# Arduino_clock.net
KiCad netlist of a schematic drawn in Altium Designer
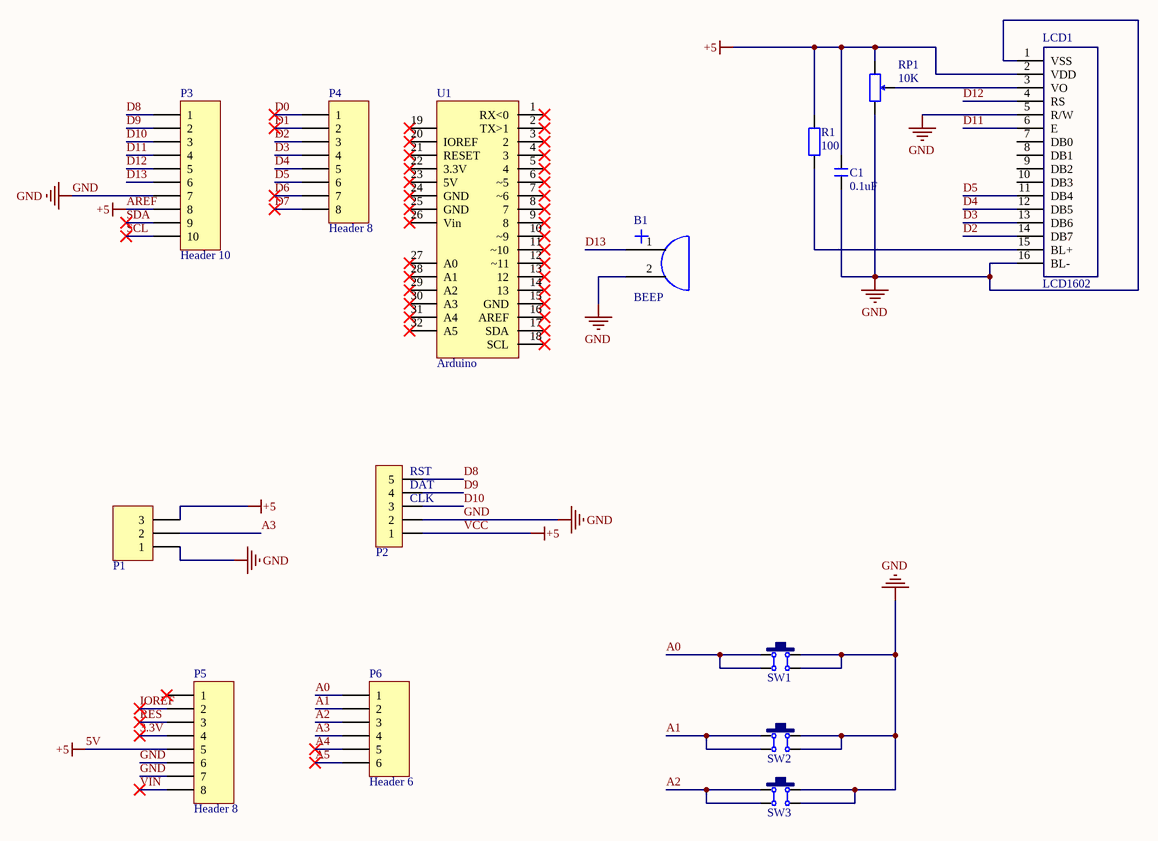
[diagram p0: Arduino_clock.SchDoc]

(export (version "E")
  (design (tool "Eeschema 10.0.6"))
  (components
    (comp (ref "B1")
      (value "BEEP")
      (footprint "Beep")
      (description "蜂鸣器")
      (libsource (lib "Fszhang") (part "BEEP"))
    )
    (comp (ref "C1")
      (value "0.1uF")
      (footprint "CY 5*7*2.5")
      (description "高压陶瓷电容，Y电容")
      (fields (field (name "版权归属") "源创客"))
      (libsource (lib "3.1   - 电阻-电容-电感") (part "C-CY"))
    )
    (comp (ref "LCD1") (value "LCD1602") (footprint "1602-1") (libsource (lib "LCD") (part "LCD1602")))
    (comp (ref "P1")
      (value "Header 3")
      (footprint "HDR2.54-LI-3P")
      (description "接插件")
      (fields (field (name "PUBLISHER") "Altium Limited"))
      (libsource (lib "Fszhang") (part "Header 3"))
    )
    (comp (ref "P2")
      (value "HDR-1X5")
      (footprint "HDR2.54-LI-5P")
      (description "5P接插件")
      (fields (field (name "版权归属") "源创客"))
      (libsource (lib "4.5   - 接插件-脚距2.54") (part "Header 5"))
    )
    (comp (ref "P3")
      (value "Header 10")
      (footprint "HDR2.54-LI-10P")
      (description "Header, 10-Pin")
      (fields (field (name "PUBLISHER") "Altium Limited"))
      (libsource (lib "Fszhang") (part "Header 10"))
    )
    (comp (ref "P4")
      (value "Header 8")
      (footprint "HDR2.54-LI-8P")
      (description "Header, 8-Pin")
      (fields (field (name "PUBLISHER") "Altium Limited"))
      (libsource (lib "Fszhang") (part "Header 8"))
    )
    (comp (ref "P5")
      (value "Header 8")
      (footprint "HDR2.54-LI-8P")
      (description "Header, 8-Pin")
      (fields (field (name "PUBLISHER") "Altium Limited"))
      (libsource (lib "Fszhang") (part "Header 8"))
    )
    (comp (ref "P6")
      (value "Header 6")
      (footprint "HDR2.54-LI-6P")
      (description "接插件")
      (fields (field (name "PUBLISHER") "Altium Limited"))
      (libsource (lib "Fszhang") (part "Header 6"))
    )
    (comp (ref "R1")
      (value "100")
      (footprint "AXIAL0.4-1/4W")
      (description "贴片电阻")
      (fields (field (name "版权归属") "源创客"))
      (libsource (lib "3.1   - 电阻-电容-电感") (part "R"))
    )
    (comp (ref "RP1")
      (value "10K")
      (footprint "RM065")
      (description "插件单联电位器")
      (fields (field (name "版权归属") "源创客"))
      (libsource (lib "3.1   - 电阻-电容-电感") (part "RP-ID"))
    )
    (comp (ref "SW1")
      (value "6x6x5")
      (footprint "TSW DIP-6*6*6")
      (description "直插6x6轻触开关")
      (fields (field (name "版权归属") "源创客"))
      (libsource (lib "5.1   - 按键-开关") (part "TSW DIP-6x6"))
    )
    (comp (ref "SW2")
      (value "6x6x5")
      (footprint "TSW DIP-6*6*6")
      (description "直插6x6轻触开关")
      (fields (field (name "版权归属") "源创客"))
      (libsource (lib "5.1   - 按键-开关") (part "TSW DIP-6x6"))
    )
    (comp (ref "SW3")
      (value "6x6x5")
      (footprint "TSW DIP-6*6*6")
      (description "直插6x6轻触开关")
      (fields (field (name "版权归属") "源创客"))
      (libsource (lib "5.1   - 按键-开关") (part "TSW DIP-6x6"))
    )
    (comp (ref "U1")
      (value "Arduino")
      (footprint "Arduino-UNO")
      (libsource (lib "LixhSch") (part "Arduino-UNO"))
    )
  )
  (nets
    (net (code "1") (name "+5") (class "Default")
      (node (ref "C1") (pin "2") (pinfunction "2_2") (pintype "passive"))
      (node (ref "LCD1") (pin "2") (pinfunction "VDD_2") (pintype "passive"))
      (node (ref "P1") (pin "3") (pinfunction "3_3") (pintype "passive"))
      (node (ref "P2") (pin "1") (pinfunction "1_1") (pintype "passive"))
      (node (ref "P3") (pin "8") (pinfunction "8_8") (pintype "passive"))
      (node (ref "P5") (pin "5") (pinfunction "5_5") (pintype "passive"))
      (node (ref "R1") (pin "2") (pinfunction "2_2") (pintype "passive"))
      (node (ref "RP1") (pin "1") (pinfunction "1_1") (pintype "passive"))
    )
    (net (code "2") (name "/3.3V") (class "Default")
      (node (ref "P5") (pin "4") (pinfunction "4_4") (pintype "passive+no_connect"))
    )
    (net (code "3") (name "/A0") (class "Default")
      (node (ref "P6") (pin "1") (pinfunction "1_1") (pintype "passive"))
      (node (ref "SW1") (pin "1") (pinfunction "1_1") (pintype "passive"))
      (node (ref "SW1") (pin "4") (pinfunction "4_4") (pintype "passive"))
    )
    (net (code "4") (name "/A1") (class "Default")
      (node (ref "P6") (pin "2") (pinfunction "2_2") (pintype "passive"))
      (node (ref "SW2") (pin "1") (pinfunction "1_1") (pintype "passive"))
      (node (ref "SW2") (pin "4") (pinfunction "4_4") (pintype "passive"))
    )
    (net (code "5") (name "/A2") (class "Default")
      (node (ref "P6") (pin "3") (pinfunction "3_3") (pintype "passive"))
      (node (ref "SW3") (pin "1") (pinfunction "1_1") (pintype "passive"))
      (node (ref "SW3") (pin "4") (pinfunction "4_4") (pintype "passive"))
    )
    (net (code "6") (name "/A3") (class "Default")
      (node (ref "P1") (pin "2") (pinfunction "2_2") (pintype "passive"))
      (node (ref "P6") (pin "4") (pinfunction "4_4") (pintype "passive"))
    )
    (net (code "7") (name "/A4") (class "Default")
      (node (ref "P6") (pin "5") (pinfunction "5_5") (pintype "passive+no_connect"))
    )
    (net (code "8") (name "/A5") (class "Default")
      (node (ref "P6") (pin "6") (pinfunction "6_6") (pintype "passive+no_connect"))
    )
    (net (code "9") (name "/D0") (class "Default")
      (node (ref "P4") (pin "1") (pinfunction "1_1") (pintype "passive+no_connect"))
    )
    (net (code "10") (name "/D1") (class "Default")
      (node (ref "P4") (pin "2") (pinfunction "2_2") (pintype "passive+no_connect"))
    )
    (net (code "11") (name "/D2") (class "Default")
      (node (ref "LCD1") (pin "14") (pinfunction "DB7_14") (pintype "passive"))
      (node (ref "P4") (pin "3") (pinfunction "3_3") (pintype "passive"))
    )
    (net (code "12") (name "/D3") (class "Default")
      (node (ref "LCD1") (pin "13") (pinfunction "DB6_13") (pintype "passive"))
      (node (ref "P4") (pin "4") (pinfunction "4_4") (pintype "passive"))
    )
    (net (code "13") (name "/D4") (class "Default")
      (node (ref "LCD1") (pin "12") (pinfunction "DB5_12") (pintype "passive"))
      (node (ref "P4") (pin "5") (pinfunction "5_5") (pintype "passive"))
    )
    (net (code "14") (name "/D5") (class "Default")
      (node (ref "LCD1") (pin "11") (pinfunction "DB4_11") (pintype "passive"))
      (node (ref "P4") (pin "6") (pinfunction "6_6") (pintype "passive"))
    )
    (net (code "15") (name "/D6") (class "Default")
      (node (ref "P4") (pin "7") (pinfunction "7_7") (pintype "passive+no_connect"))
    )
    (net (code "16") (name "/D7") (class "Default")
      (node (ref "P4") (pin "8") (pinfunction "8_8") (pintype "passive+no_connect"))
    )
    (net (code "17") (name "/D8") (class "Default")
      (node (ref "P2") (pin "5") (pinfunction "5_5") (pintype "passive"))
      (node (ref "P3") (pin "1") (pinfunction "1_1") (pintype "passive"))
    )
    (net (code "18") (name "/D9") (class "Default")
      (node (ref "P2") (pin "4") (pinfunction "4_4") (pintype "passive"))
      (node (ref "P3") (pin "2") (pinfunction "2_2") (pintype "passive"))
    )
    (net (code "19") (name "/D10") (class "Default")
      (node (ref "P2") (pin "3") (pinfunction "3_3") (pintype "passive"))
      (node (ref "P3") (pin "3") (pinfunction "3_3") (pintype "passive"))
    )
    (net (code "20") (name "/D11") (class "Default")
      (node (ref "LCD1") (pin "6") (pinfunction "E_6") (pintype "passive"))
      (node (ref "P3") (pin "4") (pinfunction "4_4") (pintype "passive"))
    )
    (net (code "21") (name "/D12") (class "Default")
      (node (ref "LCD1") (pin "4") (pinfunction "RS_4") (pintype "passive"))
      (node (ref "P3") (pin "5") (pinfunction "5_5") (pintype "passive"))
    )
    (net (code "22") (name "/D13") (class "Default")
      (node (ref "B1") (pin "1") (pinfunction "0_1") (pintype "passive"))
      (node (ref "P3") (pin "6") (pinfunction "6_6") (pintype "passive"))
    )
    (net (code "23") (name "/IOREF") (class "Default")
      (node (ref "P5") (pin "2") (pinfunction "2_2") (pintype "passive+no_connect"))
    )
    (net (code "24") (name "/RES") (class "Default")
      (node (ref "P5") (pin "3") (pinfunction "3_3") (pintype "passive+no_connect"))
    )
    (net (code "25") (name "/SCL") (class "Default")
      (node (ref "P3") (pin "10") (pinfunction "10_10") (pintype "passive+no_connect"))
    )
    (net (code "26") (name "/SDA") (class "Default")
      (node (ref "P3") (pin "9") (pinfunction "9_9") (pintype "passive+no_connect"))
    )
    (net (code "27") (name "/VIN") (class "Default")
      (node (ref "P5") (pin "8") (pinfunction "8_8") (pintype "passive+no_connect"))
    )
    (net (code "28") (name "GND") (class "Default")
      (node (ref "B1") (pin "2") (pinfunction "1_2") (pintype "passive"))
      (node (ref "C1") (pin "1") (pinfunction "1_1") (pintype "passive"))
      (node (ref "LCD1") (pin "1") (pinfunction "VSS_1") (pintype "passive"))
      (node (ref "LCD1") (pin "16") (pinfunction "BL-_16") (pintype "passive"))
      (node (ref "LCD1") (pin "5") (pinfunction "R/W_5") (pintype "passive"))
      (node (ref "P1") (pin "1") (pinfunction "1_1") (pintype "passive"))
      (node (ref "P2") (pin "2") (pinfunction "2_2") (pintype "passive"))
      (node (ref "P3") (pin "7") (pinfunction "7_7") (pintype "passive"))
      (node (ref "P5") (pin "6") (pinfunction "6_6") (pintype "passive"))
      (node (ref "P5") (pin "7") (pinfunction "7_7") (pintype "passive"))
      (node (ref "RP1") (pin "3") (pinfunction "3_3") (pintype "passive"))
      (node (ref "SW1") (pin "2") (pinfunction "2_2") (pintype "passive"))
      (node (ref "SW1") (pin "3") (pinfunction "3_3") (pintype "passive"))
      (node (ref "SW2") (pin "2") (pinfunction "2_2") (pintype "passive"))
      (node (ref "SW2") (pin "3") (pinfunction "3_3") (pintype "passive"))
      (node (ref "SW3") (pin "2") (pinfunction "2_2") (pintype "passive"))
      (node (ref "SW3") (pin "3") (pinfunction "3_3") (pintype "passive"))
    )
    (net (code "29") (name "Net-(LCD1-BL+)") (class "Default")
      (node (ref "LCD1") (pin "15") (pinfunction "BL+_15") (pintype "passive"))
      (node (ref "R1") (pin "1") (pinfunction "1_1") (pintype "passive"))
    )
    (net (code "30") (name "Net-(LCD1-VO)") (class "Default")
      (node (ref "LCD1") (pin "3") (pinfunction "VO_3") (pintype "passive"))
      (node (ref "RP1") (pin "2") (pinfunction "2_2") (pintype "passive"))
    )
    (net (code "31") (name "unconnected-(LCD1-DB0-Pad7)") (class "Default")
      (node (ref "LCD1") (pin "7") (pinfunction "DB0_7") (pintype "passive"))
    )
    (net (code "32") (name "unconnected-(LCD1-DB1-Pad8)") (class "Default")
      (node (ref "LCD1") (pin "8") (pinfunction "DB1_8") (pintype "passive"))
    )
    (net (code "33") (name "unconnected-(LCD1-DB2-Pad9)") (class "Default")
      (node (ref "LCD1") (pin "9") (pinfunction "DB2_9") (pintype "passive"))
    )
    (net (code "34") (name "unconnected-(LCD1-DB3-Pad10)") (class "Default")
      (node (ref "LCD1") (pin "10") (pinfunction "DB3_10") (pintype "passive"))
    )
    (net (code "35") (name "unconnected-(P5-Pad1)") (class "Default")
      (node (ref "P5") (pin "1") (pinfunction "1_1") (pintype "passive+no_connect"))
    )
    (net (code "36") (name "unconnected-(U1-2-Pad3)") (class "Default")
      (node (ref "U1") (pin "3") (pinfunction "2_3") (pintype "power_in+no_connect"))
    )
    (net (code "37") (name "unconnected-(U1-3-Pad4)") (class "Default")
      (node (ref "U1") (pin "4") (pinfunction "3_4") (pintype "power_in+no_connect"))
    )
    (net (code "38") (name "unconnected-(U1-3.3V-Pad22)") (class "Default")
      (node (ref "U1") (pin "22") (pinfunction "3.3V_22") (pintype "power_in+no_connect"))
    )
    (net (code "39") (name "unconnected-(U1-4-Pad5)") (class "Default")
      (node (ref "U1") (pin "5") (pinfunction "4_5") (pintype "power_in+no_connect"))
    )
    (net (code "40") (name "unconnected-(U1-5V-Pad23)") (class "Default")
      (node (ref "U1") (pin "23") (pinfunction "5V_23") (pintype "power_in+no_connect"))
    )
    (net (code "41") (name "unconnected-(U1-7-Pad8)") (class "Default")
      (node (ref "U1") (pin "8") (pinfunction "7_8") (pintype "power_in+no_connect"))
    )
    (net (code "42") (name "unconnected-(U1-8-Pad9)") (class "Default")
      (node (ref "U1") (pin "9") (pinfunction "8_9") (pintype "power_in+no_connect"))
    )
    (net (code "43") (name "unconnected-(U1-12-Pad13)") (class "Default")
      (node (ref "U1") (pin "13") (pinfunction "12_13") (pintype "power_in+no_connect"))
    )
    (net (code "44") (name "unconnected-(U1-13-Pad14)") (class "Default")
      (node (ref "U1") (pin "14") (pinfunction "13_14") (pintype "power_in+no_connect"))
    )
    (net (code "45") (name "unconnected-(U1-A0-Pad27)") (class "Default")
      (node (ref "U1") (pin "27") (pinfunction "A0_27") (pintype "power_in+no_connect"))
    )
    (net (code "46") (name "unconnected-(U1-A1-Pad28)") (class "Default")
      (node (ref "U1") (pin "28") (pinfunction "A1_28") (pintype "power_in+no_connect"))
    )
    (net (code "47") (name "unconnected-(U1-A2-Pad29)") (class "Default")
      (node (ref "U1") (pin "29") (pinfunction "A2_29") (pintype "power_in+no_connect"))
    )
    (net (code "48") (name "unconnected-(U1-A3-Pad30)") (class "Default")
      (node (ref "U1") (pin "30") (pinfunction "A3_30") (pintype "power_in+no_connect"))
    )
    (net (code "49") (name "unconnected-(U1-A4-Pad31)") (class "Default")
      (node (ref "U1") (pin "31") (pinfunction "A4_31") (pintype "power_in+no_connect"))
    )
    (net (code "50") (name "unconnected-(U1-A5-Pad32)") (class "Default")
      (node (ref "U1") (pin "32") (pinfunction "A5_32") (pintype "power_in+no_connect"))
    )
    (net (code "51") (name "unconnected-(U1-AREF-Pad16)") (class "Default")
      (node (ref "U1") (pin "16") (pinfunction "AREF_16") (pintype "power_in+no_connect"))
    )
    (net (code "52") (name "unconnected-(U1-GND-Pad15)") (class "Default")
      (node (ref "U1") (pin "15") (pinfunction "GND_15") (pintype "power_in+no_connect"))
    )
    (net (code "53") (name "unconnected-(U1-GND-Pad24)") (class "Default")
      (node (ref "U1") (pin "24") (pinfunction "GND_24") (pintype "power_in+no_connect"))
    )
    (net (code "54") (name "unconnected-(U1-GND-Pad25)") (class "Default")
      (node (ref "U1") (pin "25") (pinfunction "GND_25") (pintype "power_in+no_connect"))
    )
    (net (code "55") (name "unconnected-(U1-IOREF-Pad20)") (class "Default")
      (node (ref "U1") (pin "20") (pinfunction "IOREF_20") (pintype "power_in+no_connect"))
    )
    (net (code "56") (name "unconnected-(U1-Pad19)") (class "Default")
      (node (ref "U1") (pin "19") (pintype "power_in+no_connect"))
    )
    (net (code "57") (name "unconnected-(U1-RESET-Pad21)") (class "Default")
      (node (ref "U1") (pin "21") (pinfunction "RESET_21") (pintype "power_in+no_connect"))
    )
    (net (code "58") (name "unconnected-(U1-RX<0-Pad1)") (class "Default")
      (node (ref "U1") (pin "1") (pinfunction "RX<0_1") (pintype "power_in+no_connect"))
    )
    (net (code "59") (name "unconnected-(U1-SCL-Pad18)") (class "Default")
      (node (ref "U1") (pin "18") (pinfunction "SCL_18") (pintype "power_in+no_connect"))
    )
    (net (code "60") (name "unconnected-(U1-SDA-Pad17)") (class "Default")
      (node (ref "U1") (pin "17") (pinfunction "SDA_17") (pintype "power_in+no_connect"))
    )
    (net (code "61") (name "unconnected-(U1-TX>1-Pad2)") (class "Default")
      (node (ref "U1") (pin "2") (pinfunction "TX>1_2") (pintype "power_in+no_connect"))
    )
    (net (code "62") (name "unconnected-(U1-Vin-Pad26)") (class "Default")
      (node (ref "U1") (pin "26") (pinfunction "Vin_26") (pintype "power_in+no_connect"))
    )
    (net (code "63") (name "unconnected-(U1-~5-Pad6)") (class "Default")
      (node (ref "U1") (pin "6") (pinfunction "~5_6") (pintype "power_in+no_connect"))
    )
    (net (code "64") (name "unconnected-(U1-~6-Pad7)") (class "Default")
      (node (ref "U1") (pin "7") (pinfunction "~6_7") (pintype "power_in+no_connect"))
    )
    (net (code "65") (name "unconnected-(U1-~9-Pad10)") (class "Default")
      (node (ref "U1") (pin "10") (pinfunction "~9_10") (pintype "power_in+no_connect"))
    )
    (net (code "66") (name "unconnected-(U1-~10-Pad11)") (class "Default")
      (node (ref "U1") (pin "11") (pinfunction "~10_11") (pintype "power_in+no_connect"))
    )
    (net (code "67") (name "unconnected-(U1-~11-Pad12)") (class "Default")
      (node (ref "U1") (pin "12") (pinfunction "~11_12") (pintype "power_in+no_connect"))
    )
  )
)
